# OUTPUT.net
KiCad netlist of a schematic drawn in Altium Designer
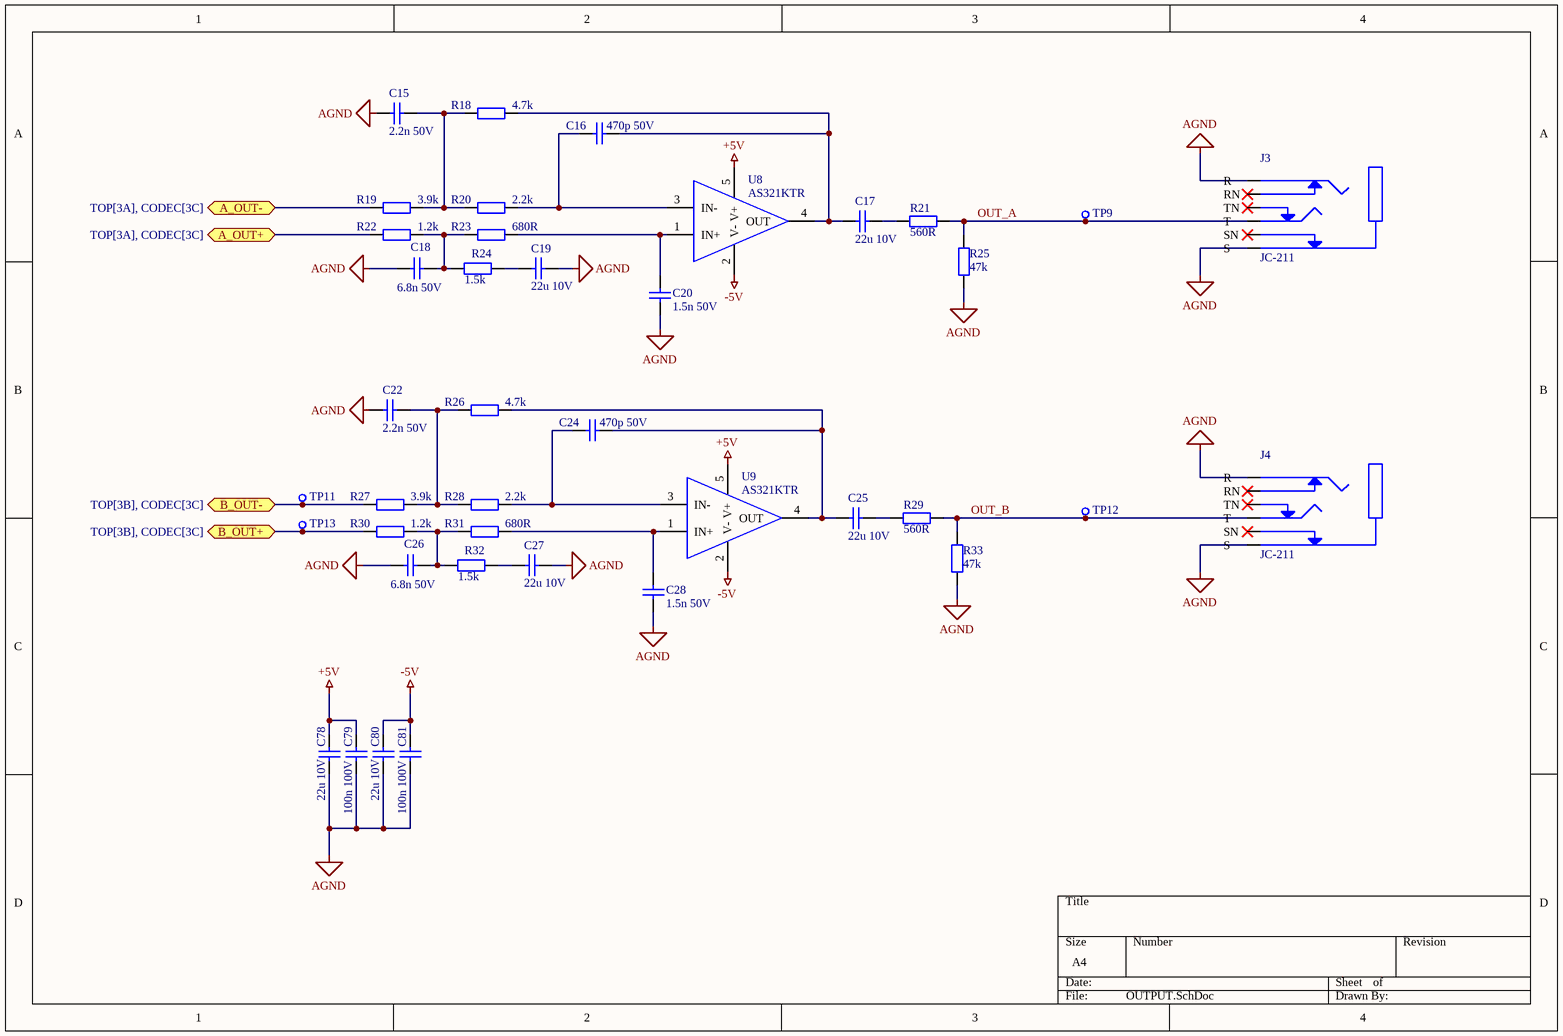
[diagram p0: OUTPUT.SchDoc]

(export (version "E")
  (design (tool "Eeschema 10.0.6"))
  (components
    (comp (ref "C15")
      (value "2.2n 50V")
      (footprint "FOOTPRINTS:CAPACITOR 0805")
      (description "Capacitor: ceramic; MLCC; 2.2nF; 50V; X7R; ±10%; SMD; 0805")
      (fields
        (field (name "MANUFACTURER") "KYOCERA AVX")
        (field (name "MANUFACTURER PART NUMBER") "08055C222KAT2A")
      )
      (libsource (lib "SYMBOLS") (part "Capacitor 2.2n 50V ±2% X7R 0805"))
    )
    (comp (ref "C16")
      (value "470p 50V")
      (footprint "FOOTPRINTS:CAPACITOR 0805")
      (description "Capacitor: ceramic; MLCC; 470pF; 50V; X7R; ±10%; SMD; 0805")
      (fields
        (field (name "MANUFACTURER") "KEMET")
        (field (name "MANUFACTURER PART NUMBER") "C0805C471K5RAC")
      )
      (libsource (lib "SYMBOLS") (part "Capacitor 470p 50V 10% X7R 0805"))
    )
    (comp (ref "C17")
      (value "22u 10V")
      (footprint "FOOTPRINTS:CAPACITOR 0805")
      (description "Capacitor: ceramic; 22uF; 10V; X5R; ±20%; SMD; 0805")
      (fields
        (field (name "MANUFACTURER") "SAMSUNG")
        (field (name "MANUFACTURER PART NUMBER") "CL21A226MPQNNNE")
      )
      (libsource (lib "SYMBOLS") (part "Capacitor 22u 10V 20% X5R 0805"))
    )
    (comp (ref "C18")
      (value "6.8n 50V")
      (footprint "FOOTPRINTS:CAPACITOR 0805")
      (description "Capacitor: ceramic; MLCC; 6.8nF; 50V; X7R; ±10%; SMD; 0805")
      (fields
        (field (name "MANUFACTURER") "KYOCERA AVX")
        (field (name "MANUFACTURER PART NUMBER") "08055C682KAT2A")
      )
      (libsource (lib "SYMBOLS") (part "Capacitor 6.8n 50V ±2% X7R 0805"))
    )
    (comp (ref "C19")
      (value "22u 10V")
      (footprint "FOOTPRINTS:CAPACITOR 0805")
      (description "Capacitor: ceramic; 22uF; 10V; X5R; ±20%; SMD; 0805")
      (fields
        (field (name "MANUFACTURER") "SAMSUNG")
        (field (name "MANUFACTURER PART NUMBER") "CL21A226MPQNNNE")
      )
      (libsource (lib "SYMBOLS") (part "Capacitor 22u 10V 20% X5R 0805"))
    )
    (comp (ref "C20")
      (value "1.5n 50V")
      (footprint "FOOTPRINTS:CAPACITOR 0805")
      (description "Capacitor: ceramic; MLCC; 1.5nF; 50V; X7R; ±10%; SMD; 0805")
      (fields
        (field (name "MANUFACTURER") "KYOCERA AVX")
        (field (name "MANUFACTURER PART NUMBER") "08055C152KAT2A")
      )
      (libsource (lib "SYMBOLS") (part "Capacitor 1.5n 50V ±2% X7R 0805"))
    )
    (comp (ref "C22")
      (value "2.2n 50V")
      (footprint "FOOTPRINTS:CAPACITOR 0805")
      (description "Capacitor: ceramic; MLCC; 2.2nF; 50V; X7R; ±10%; SMD; 0805")
      (fields
        (field (name "MANUFACTURER") "KYOCERA AVX")
        (field (name "MANUFACTURER PART NUMBER") "08055C222KAT2A")
      )
      (libsource (lib "SYMBOLS") (part "Capacitor 2.2n 50V ±2% X7R 0805"))
    )
    (comp (ref "C24")
      (value "470p 50V")
      (footprint "FOOTPRINTS:CAPACITOR 0805")
      (description "Capacitor: ceramic; MLCC; 470pF; 50V; X7R; ±10%; SMD; 0805")
      (fields
        (field (name "MANUFACTURER") "KEMET")
        (field (name "MANUFACTURER PART NUMBER") "C0805C471K5RAC")
      )
      (libsource (lib "SYMBOLS") (part "Capacitor 470p 50V 10% X7R 0805"))
    )
    (comp (ref "C25")
      (value "22u 10V")
      (footprint "FOOTPRINTS:CAPACITOR 0805")
      (description "Capacitor: ceramic; 22uF; 10V; X5R; ±20%; SMD; 0805")
      (fields
        (field (name "MANUFACTURER") "SAMSUNG")
        (field (name "MANUFACTURER PART NUMBER") "CL21A226MPQNNNE")
      )
      (libsource (lib "SYMBOLS") (part "Capacitor 22u 10V 20% X5R 0805"))
    )
    (comp (ref "C26")
      (value "6.8n 50V")
      (footprint "FOOTPRINTS:CAPACITOR 0805")
      (description "Capacitor: ceramic; MLCC; 6.8nF; 50V; X7R; ±10%; SMD; 0805")
      (fields
        (field (name "MANUFACTURER") "KYOCERA AVX")
        (field (name "MANUFACTURER PART NUMBER") "08055C682KAT2A")
      )
      (libsource (lib "SYMBOLS") (part "Capacitor 6.8n 50V ±2% X7R 0805"))
    )
    (comp (ref "C27")
      (value "22u 10V")
      (footprint "FOOTPRINTS:CAPACITOR 0805")
      (description "Capacitor: ceramic; 22uF; 10V; X5R; ±20%; SMD; 0805")
      (fields
        (field (name "MANUFACTURER") "SAMSUNG")
        (field (name "MANUFACTURER PART NUMBER") "CL21A226MPQNNNE")
      )
      (libsource (lib "SYMBOLS") (part "Capacitor 22u 10V 20% X5R 0805"))
    )
    (comp (ref "C28")
      (value "1.5n 50V")
      (footprint "FOOTPRINTS:CAPACITOR 0805")
      (description "Capacitor: ceramic; MLCC; 1.5nF; 50V; X7R; ±10%; SMD; 0805")
      (fields
        (field (name "MANUFACTURER") "KYOCERA AVX")
        (field (name "MANUFACTURER PART NUMBER") "08055C152KAT2A")
      )
      (libsource (lib "SYMBOLS") (part "Capacitor 1.5n 50V ±2% X7R 0805"))
    )
    (comp (ref "C78")
      (value "22u 10V")
      (footprint "FOOTPRINTS:CAPACITOR 0805")
      (description "Capacitor: ceramic; 22uF; 10V; X5R; ±20%; SMD; 0805")
      (fields
        (field (name "MANUFACTURER") "SAMSUNG")
        (field (name "MANUFACTURER PART NUMBER") "CL21A226MPQNNNE")
      )
      (libsource (lib "SYMBOLS") (part "Capacitor 22u 10V 20% X5R 0805"))
    )
    (comp (ref "C79")
      (value "100n 100V")
      (footprint "FOOTPRINTS:CAPACITOR 0805")
      (description "Capacitor: ceramic; MLCC; 100nF; 100V; X7R; ±10%; SMD; 0805")
      (fields
        (field (name "MANUFACTURER") "YAGEO")
        (field (name "MANUFACTURER PART NUMBER") "CC0805KKX7R0BB104")
      )
      (libsource (lib "SYMBOLS") (part "Capacitor 100n 100V 10% X7R 0805"))
    )
    (comp (ref "C80")
      (value "22u 10V")
      (footprint "FOOTPRINTS:CAPACITOR 0805")
      (description "Capacitor: ceramic; 22uF; 10V; X5R; ±20%; SMD; 0805")
      (fields
        (field (name "MANUFACTURER") "SAMSUNG")
        (field (name "MANUFACTURER PART NUMBER") "CL21A226MPQNNNE")
      )
      (libsource (lib "SYMBOLS") (part "Capacitor 22u 10V 20% X5R 0805"))
    )
    (comp (ref "C81")
      (value "100n 100V")
      (footprint "FOOTPRINTS:CAPACITOR 0805")
      (description "Capacitor: ceramic; MLCC; 100nF; 100V; X7R; ±10%; SMD; 0805")
      (fields
        (field (name "MANUFACTURER") "YAGEO")
        (field (name "MANUFACTURER PART NUMBER") "CC0805KKX7R0BB104")
      )
      (libsource (lib "SYMBOLS") (part "Capacitor 100n 100V 10% X7R 0805"))
    )
    (comp (ref "J3")
      (value "JC-211")
      (footprint "FOOTPRINTS:AMPHENOL ACJM-MHDR")
      (description "Socket; Jack 6,3mm; female; mono; ways: 2; for panel mounting; THT")
      (fields (field (name "MANUFACTURER") "NINIGI"))
      (libsource (lib "SYMBOLS") (part "Mechanical Jack 6.3mm Socket PCB THT JC-211"))
    )
    (comp (ref "J4")
      (value "JC-211")
      (footprint "FOOTPRINTS:AMPHENOL ACJM-MHDR")
      (description "Socket; Jack 6,3mm; female; mono; ways: 2; for panel mounting; THT")
      (fields (field (name "MANUFACTURER") "NINIGI"))
      (libsource (lib "SYMBOLS") (part "Mechanical Jack 6.3mm Socket PCB THT JC-211"))
    )
    (comp (ref "R18")
      (value "4.7k")
      (footprint "FOOTPRINTS:RESISTOR 0805")
      (description "Resistor: thick film; SMD; 0805; 4.7kΩ; 0.125W; ±1%; -55÷155°C")
      (fields
        (field (name "MANUFACTURER") "Yageo")
        (field (name "MANUFACTURER PART NUMBER") "RC0805FR-074K7")
      )
      (libsource (lib "SYMBOLS") (part "Resistor 4.7k 1% 1/8W 0805"))
    )
    (comp (ref "R19")
      (value "3.9k")
      (footprint "FOOTPRINTS:RESISTOR 0805")
      (description "Resistor: thick film; SMD; 0805; 3.9kkΩ; 0.125W; ±1%; -55÷155°C")
      (fields
        (field (name "MANUFACTURER") "Yageo")
        (field (name "MANUFACTURER PART NUMBER") "RC0805FR-073K9")
      )
      (libsource (lib "SYMBOLS") (part "Resistor 3.9k 1% 1/8W 0805"))
    )
    (comp (ref "R20")
      (value "2.2k")
      (footprint "FOOTPRINTS:RESISTOR 0805")
      (description "Resistor: thick film; SMD; 0805; 2.2kΩ; 0.125W; ±1%; -55÷155°C")
      (fields
        (field (name "MANUFACTURER") "Yageo")
        (field (name "MANUFACTURER PART NUMBER") "RC0805FR-072K2")
      )
      (libsource (lib "SYMBOLS") (part "Resistor 2.2k 1% 1/8W 0805"))
    )
    (comp (ref "R21")
      (value "560R")
      (footprint "FOOTPRINTS:RESISTOR 0805")
      (description "Resistor: thick film; SMD; 0805; 560Ω; 0.125W; ±1%; -55÷155°C")
      (fields
        (field (name "MANUFACTURER") "Yageo")
        (field (name "MANUFACTURER PART NUMBER") "RC0805FR-07560R")
      )
      (libsource (lib "SYMBOLS") (part "Resistor 560R 1% 1/8W 0805"))
    )
    (comp (ref "R22")
      (value "1.2k")
      (footprint "FOOTPRINTS:RESISTOR 0805")
      (description "Resistor: thick film; SMD; 0805; 1.2kΩ; 0.125W; ±1%; -55÷155°C")
      (fields
        (field (name "MANUFACTURER") "Yageo")
        (field (name "MANUFACTURER PART NUMBER") "RC0805FR-071K2")
      )
      (libsource (lib "SYMBOLS") (part "Resistor 1.2k 1% 1/8W 0805"))
    )
    (comp (ref "R23")
      (value "680R")
      (footprint "FOOTPRINTS:RESISTOR 0805")
      (description "Resistor: thick film; SMD; 0805; 680Ω; 0.125W; ±1%; -55÷155°C")
      (fields
        (field (name "MANUFACTURER") "Yageo")
        (field (name "MANUFACTURER PART NUMBER") "RC0805FR-07680R")
      )
      (libsource (lib "SYMBOLS") (part "Resistor 680R 1% 1/8W 0805"))
    )
    (comp (ref "R24")
      (value "1.5k")
      (footprint "FOOTPRINTS:RESISTOR 0805")
      (description "Resistor: thick film; SMD; 0805; 1.5kΩ; 0.125W; ±1%; -55÷155°C")
      (fields
        (field (name "MANUFACTURER") "Yageo")
        (field (name "MANUFACTURER PART NUMBER") "RC0805FR-071K5")
      )
      (libsource (lib "SYMBOLS") (part "Resistor 1.5k 1% 1/8W 0805"))
    )
    (comp (ref "R25")
      (value "47k")
      (footprint "FOOTPRINTS:RESISTOR 0805")
      (description "Resistor: thick film; SMD; 0805; 47kΩ; 0.125W; ±1%; -55÷155°C")
      (fields
        (field (name "MANUFACTURER") "Yageo")
        (field (name "MANUFACTURER PART NUMBER") "RC0805FR-0747K")
      )
      (libsource (lib "SYMBOLS") (part "Resistor 47k 1% 1/8W 0805"))
    )
    (comp (ref "R26")
      (value "4.7k")
      (footprint "FOOTPRINTS:RESISTOR 0805")
      (description "Resistor: thick film; SMD; 0805; 4.7kΩ; 0.125W; ±1%; -55÷155°C")
      (fields
        (field (name "MANUFACTURER") "Yageo")
        (field (name "MANUFACTURER PART NUMBER") "RC0805FR-074K7")
      )
      (libsource (lib "SYMBOLS") (part "Resistor 4.7k 1% 1/8W 0805"))
    )
    (comp (ref "R27")
      (value "3.9k")
      (footprint "FOOTPRINTS:RESISTOR 0805")
      (description "Resistor: thick film; SMD; 0805; 3.9kkΩ; 0.125W; ±1%; -55÷155°C")
      (fields
        (field (name "MANUFACTURER") "Yageo")
        (field (name "MANUFACTURER PART NUMBER") "RC0805FR-073K9")
      )
      (libsource (lib "SYMBOLS") (part "Resistor 3.9k 1% 1/8W 0805"))
    )
    (comp (ref "R28")
      (value "2.2k")
      (footprint "FOOTPRINTS:RESISTOR 0805")
      (description "Resistor: thick film; SMD; 0805; 2.2kΩ; 0.125W; ±1%; -55÷155°C")
      (fields
        (field (name "MANUFACTURER") "Yageo")
        (field (name "MANUFACTURER PART NUMBER") "RC0805FR-072K2")
      )
      (libsource (lib "SYMBOLS") (part "Resistor 2.2k 1% 1/8W 0805"))
    )
    (comp (ref "R29")
      (value "560R")
      (footprint "FOOTPRINTS:RESISTOR 0805")
      (description "Resistor: thick film; SMD; 0805; 560Ω; 0.125W; ±1%; -55÷155°C")
      (fields
        (field (name "MANUFACTURER") "Yageo")
        (field (name "MANUFACTURER PART NUMBER") "RC0805FR-07560R")
      )
      (libsource (lib "SYMBOLS") (part "Resistor 560R 1% 1/8W 0805"))
    )
    (comp (ref "R30")
      (value "1.2k")
      (footprint "FOOTPRINTS:RESISTOR 0805")
      (description "Resistor: thick film; SMD; 0805; 1.2kΩ; 0.125W; ±1%; -55÷155°C")
      (fields
        (field (name "MANUFACTURER") "Yageo")
        (field (name "MANUFACTURER PART NUMBER") "RC0805FR-071K2")
      )
      (libsource (lib "SYMBOLS") (part "Resistor 1.2k 1% 1/8W 0805"))
    )
    (comp (ref "R31")
      (value "680R")
      (footprint "FOOTPRINTS:RESISTOR 0805")
      (description "Resistor: thick film; SMD; 0805; 680Ω; 0.125W; ±1%; -55÷155°C")
      (fields
        (field (name "MANUFACTURER") "Yageo")
        (field (name "MANUFACTURER PART NUMBER") "RC0805FR-07680R")
      )
      (libsource (lib "SYMBOLS") (part "Resistor 680R 1% 1/8W 0805"))
    )
    (comp (ref "R32")
      (value "1.5k")
      (footprint "FOOTPRINTS:RESISTOR 0805")
      (description "Resistor: thick film; SMD; 0805; 1.5kΩ; 0.125W; ±1%; -55÷155°C")
      (fields
        (field (name "MANUFACTURER") "Yageo")
        (field (name "MANUFACTURER PART NUMBER") "RC0805FR-071K5")
      )
      (libsource (lib "SYMBOLS") (part "Resistor 1.5k 1% 1/8W 0805"))
    )
    (comp (ref "R33")
      (value "47k")
      (footprint "FOOTPRINTS:RESISTOR 0805")
      (description "Resistor: thick film; SMD; 0805; 47kΩ; 0.125W; ±1%; -55÷155°C")
      (fields
        (field (name "MANUFACTURER") "Yageo")
        (field (name "MANUFACTURER PART NUMBER") "RC0805FR-0747K")
      )
      (libsource (lib "SYMBOLS") (part "Resistor 47k 1% 1/8W 0805"))
    )
    (comp (ref "TP9")
      (value "1mm")
      (footprint "FOOTPRINTS:TEST POINT 1MM")
      (description "Tesp Point 1mm")
      (libsource (lib "SYMBOLS") (part "Mechanical Test Point 1mm"))
    )
    (comp (ref "TP11")
      (value "1mm")
      (footprint "FOOTPRINTS:TEST POINT 1MM")
      (description "Tesp Point 1mm")
      (libsource (lib "SYMBOLS") (part "Mechanical Test Point 1mm"))
    )
    (comp (ref "TP12")
      (value "1mm")
      (footprint "FOOTPRINTS:TEST POINT 1MM")
      (description "Tesp Point 1mm")
      (libsource (lib "SYMBOLS") (part "Mechanical Test Point 1mm"))
    )
    (comp (ref "TP13")
      (value "1mm")
      (footprint "FOOTPRINTS:TEST POINT 1MM")
      (description "Tesp Point 1mm")
      (libsource (lib "SYMBOLS") (part "Mechanical Test Point 1mm"))
    )
    (comp (ref "U8")
      (value "AS321KTR")
      (footprint "FOOTPRINTS:SOT23-5")
      (description "IC: operational amplifier; 3÷36V; Ch: 1; SOT23-5; reel,tape")
      (fields
        (field (name "MANUFACTURER") "DIODES INCORPORATED")
        (field (name "MANUFACTURER PART NUMBER") "AS321KTR-G1")
      )
      (libsource (lib "SYMBOLS") (part "IC Op-Amp Single AS321KTR SOT23-5"))
    )
    (comp (ref "U9")
      (value "AS321KTR")
      (footprint "FOOTPRINTS:SOT23-5")
      (description "IC: operational amplifier; 3÷36V; Ch: 1; SOT23-5; reel,tape")
      (fields
        (field (name "MANUFACTURER") "DIODES INCORPORATED")
        (field (name "MANUFACTURER PART NUMBER") "AS321KTR-G1")
      )
      (libsource (lib "SYMBOLS") (part "IC Op-Amp Single AS321KTR SOT23-5"))
    )
  )
  (nets
    (net (code "1") (name "+5V") (class "Default")
      (node (ref "C78") (pin "2") (pinfunction "2_2") (pintype "passive"))
      (node (ref "C79") (pin "2") (pinfunction "2_2") (pintype "passive"))
      (node (ref "U8") (pin "5") (pinfunction "V+_5") (pintype "passive"))
      (node (ref "U9") (pin "5") (pinfunction "V+_5") (pintype "passive"))
    )
    (net (code "2") (name "-5V") (class "Default")
      (node (ref "C80") (pin "2") (pinfunction "2_2") (pintype "passive"))
      (node (ref "C81") (pin "2") (pinfunction "2_2") (pintype "passive"))
      (node (ref "U8") (pin "2") (pinfunction "V-_2") (pintype "passive"))
      (node (ref "U9") (pin "2") (pinfunction "V-_2") (pintype "passive"))
    )
    (net (code "3") (name "/A_OUT+") (class "Default")
      (node (ref "R22") (pin "1") (pinfunction "1_1") (pintype "passive"))
    )
    (net (code "4") (name "/A_OUT-") (class "Default")
      (node (ref "R19") (pin "1") (pinfunction "1_1") (pintype "passive"))
    )
    (net (code "5") (name "/B_OUT+") (class "Default")
      (node (ref "R30") (pin "1") (pinfunction "1_1") (pintype "passive"))
      (node (ref "TP13") (pin "1") (pinfunction "1_1") (pintype "passive"))
    )
    (net (code "6") (name "/B_OUT-") (class "Default")
      (node (ref "R27") (pin "1") (pinfunction "1_1") (pintype "passive"))
      (node (ref "TP11") (pin "1") (pinfunction "1_1") (pintype "passive"))
    )
    (net (code "7") (name "/OUT_A") (class "Default")
      (node (ref "J3") (pin "3") (pinfunction "T_3") (pintype "passive"))
      (node (ref "R21") (pin "2") (pinfunction "2_2") (pintype "passive"))
      (node (ref "R25") (pin "2") (pinfunction "2_2") (pintype "passive"))
      (node (ref "TP9") (pin "1") (pinfunction "1_1") (pintype "passive"))
    )
    (net (code "8") (name "/OUT_B") (class "Default")
      (node (ref "J4") (pin "3") (pinfunction "T_3") (pintype "passive"))
      (node (ref "R29") (pin "2") (pinfunction "2_2") (pintype "passive"))
      (node (ref "R33") (pin "2") (pinfunction "2_2") (pintype "passive"))
      (node (ref "TP12") (pin "1") (pinfunction "1_1") (pintype "passive"))
    )
    (net (code "9") (name "AGND") (class "Default")
      (node (ref "C15") (pin "1") (pinfunction "1_1") (pintype "passive"))
      (node (ref "C18") (pin "1") (pinfunction "1_1") (pintype "passive"))
      (node (ref "C19") (pin "2") (pinfunction "2_2") (pintype "passive"))
      (node (ref "C20") (pin "1") (pinfunction "1_1") (pintype "passive"))
      (node (ref "C22") (pin "1") (pinfunction "1_1") (pintype "passive"))
      (node (ref "C26") (pin "1") (pinfunction "1_1") (pintype "passive"))
      (node (ref "C27") (pin "2") (pinfunction "2_2") (pintype "passive"))
      (node (ref "C28") (pin "1") (pinfunction "1_1") (pintype "passive"))
      (node (ref "C78") (pin "1") (pinfunction "1_1") (pintype "passive"))
      (node (ref "C79") (pin "1") (pinfunction "1_1") (pintype "passive"))
      (node (ref "C80") (pin "1") (pinfunction "1_1") (pintype "passive"))
      (node (ref "C81") (pin "1") (pinfunction "1_1") (pintype "passive"))
      (node (ref "J3") (pin "1") (pinfunction "S_1") (pintype "passive"))
      (node (ref "J3") (pin "2") (pinfunction "R_2") (pintype "passive"))
      (node (ref "J4") (pin "1") (pinfunction "S_1") (pintype "passive"))
      (node (ref "J4") (pin "2") (pinfunction "R_2") (pintype "passive"))
      (node (ref "R25") (pin "1") (pinfunction "1_1") (pintype "passive"))
      (node (ref "R33") (pin "1") (pinfunction "1_1") (pintype "passive"))
    )
    (net (code "10") (name "Net-(C15-Pad2)") (class "Default")
      (node (ref "C15") (pin "2") (pinfunction "2_2") (pintype "passive"))
      (node (ref "R18") (pin "1") (pinfunction "1_1") (pintype "passive"))
      (node (ref "R19") (pin "2") (pinfunction "2_2") (pintype "passive"))
      (node (ref "R20") (pin "1") (pinfunction "1_1") (pintype "passive"))
    )
    (net (code "11") (name "Net-(C17-Pad2)") (class "Default")
      (node (ref "C17") (pin "2") (pinfunction "2_2") (pintype "passive"))
      (node (ref "R21") (pin "1") (pinfunction "1_1") (pintype "passive"))
    )
    (net (code "12") (name "Net-(C18-Pad2)") (class "Default")
      (node (ref "C18") (pin "2") (pinfunction "2_2") (pintype "passive"))
      (node (ref "R22") (pin "2") (pinfunction "2_2") (pintype "passive"))
      (node (ref "R23") (pin "1") (pinfunction "1_1") (pintype "passive"))
      (node (ref "R24") (pin "1") (pinfunction "1_1") (pintype "passive"))
    )
    (net (code "13") (name "Net-(C19-Pad1)") (class "Default")
      (node (ref "C19") (pin "1") (pinfunction "1_1") (pintype "passive"))
      (node (ref "R24") (pin "2") (pinfunction "2_2") (pintype "passive"))
    )
    (net (code "14") (name "Net-(C22-Pad2)") (class "Default")
      (node (ref "C22") (pin "2") (pinfunction "2_2") (pintype "passive"))
      (node (ref "R26") (pin "1") (pinfunction "1_1") (pintype "passive"))
      (node (ref "R27") (pin "2") (pinfunction "2_2") (pintype "passive"))
      (node (ref "R28") (pin "1") (pinfunction "1_1") (pintype "passive"))
    )
    (net (code "15") (name "Net-(C25-Pad2)") (class "Default")
      (node (ref "C25") (pin "2") (pinfunction "2_2") (pintype "passive"))
      (node (ref "R29") (pin "1") (pinfunction "1_1") (pintype "passive"))
    )
    (net (code "16") (name "Net-(C26-Pad2)") (class "Default")
      (node (ref "C26") (pin "2") (pinfunction "2_2") (pintype "passive"))
      (node (ref "R30") (pin "2") (pinfunction "2_2") (pintype "passive"))
      (node (ref "R31") (pin "1") (pinfunction "1_1") (pintype "passive"))
      (node (ref "R32") (pin "1") (pinfunction "1_1") (pintype "passive"))
    )
    (net (code "17") (name "Net-(C27-Pad1)") (class "Default")
      (node (ref "C27") (pin "1") (pinfunction "1_1") (pintype "passive"))
      (node (ref "R32") (pin "2") (pinfunction "2_2") (pintype "passive"))
    )
    (net (code "18") (name "Net-(U8-IN+)") (class "Default")
      (node (ref "C20") (pin "2") (pinfunction "2_2") (pintype "passive"))
      (node (ref "R23") (pin "2") (pinfunction "2_2") (pintype "passive"))
      (node (ref "U8") (pin "1") (pinfunction "IN+_1") (pintype "passive"))
    )
    (net (code "19") (name "Net-(U8-IN-)") (class "Default")
      (node (ref "C16") (pin "1") (pinfunction "1_1") (pintype "passive"))
      (node (ref "R20") (pin "2") (pinfunction "2_2") (pintype "passive"))
      (node (ref "U8") (pin "3") (pinfunction "IN-_3") (pintype "passive"))
    )
    (net (code "20") (name "Net-(U8-OUT)") (class "Default")
      (node (ref "C16") (pin "2") (pinfunction "2_2") (pintype "passive"))
      (node (ref "C17") (pin "1") (pinfunction "1_1") (pintype "passive"))
      (node (ref "R18") (pin "2") (pinfunction "2_2") (pintype "passive"))
      (node (ref "U8") (pin "4") (pinfunction "OUT_4") (pintype "passive"))
    )
    (net (code "21") (name "Net-(U9-IN+)") (class "Default")
      (node (ref "C28") (pin "2") (pinfunction "2_2") (pintype "passive"))
      (node (ref "R31") (pin "2") (pinfunction "2_2") (pintype "passive"))
      (node (ref "U9") (pin "1") (pinfunction "IN+_1") (pintype "passive"))
    )
    (net (code "22") (name "Net-(U9-IN-)") (class "Default")
      (node (ref "C24") (pin "1") (pinfunction "1_1") (pintype "passive"))
      (node (ref "R28") (pin "2") (pinfunction "2_2") (pintype "passive"))
      (node (ref "U9") (pin "3") (pinfunction "IN-_3") (pintype "passive"))
    )
    (net (code "23") (name "Net-(U9-OUT)") (class "Default")
      (node (ref "C24") (pin "2") (pinfunction "2_2") (pintype "passive"))
      (node (ref "C25") (pin "1") (pinfunction "1_1") (pintype "passive"))
      (node (ref "R26") (pin "2") (pinfunction "2_2") (pintype "passive"))
      (node (ref "U9") (pin "4") (pinfunction "OUT_4") (pintype "passive"))
    )
    (net (code "24") (name "unconnected-(J3-RN-Pad5)") (class "Default")
      (node (ref "J3") (pin "5") (pinfunction "RN_5") (pintype "passive+no_connect"))
    )
    (net (code "25") (name "unconnected-(J3-SN-Pad6)") (class "Default")
      (node (ref "J3") (pin "6") (pinfunction "SN_6") (pintype "passive+no_connect"))
    )
    (net (code "26") (name "unconnected-(J3-TN-Pad4)") (class "Default")
      (node (ref "J3") (pin "4") (pinfunction "TN_4") (pintype "passive+no_connect"))
    )
    (net (code "27") (name "unconnected-(J4-RN-Pad5)") (class "Default")
      (node (ref "J4") (pin "5") (pinfunction "RN_5") (pintype "passive+no_connect"))
    )
    (net (code "28") (name "unconnected-(J4-SN-Pad6)") (class "Default")
      (node (ref "J4") (pin "6") (pinfunction "SN_6") (pintype "passive+no_connect"))
    )
    (net (code "29") (name "unconnected-(J4-TN-Pad4)") (class "Default")
      (node (ref "J4") (pin "4") (pinfunction "TN_4") (pintype "passive+no_connect"))
    )
  )
)
